# temp-sensor.net
KiCad netlist of a schematic drawn in EAGLE
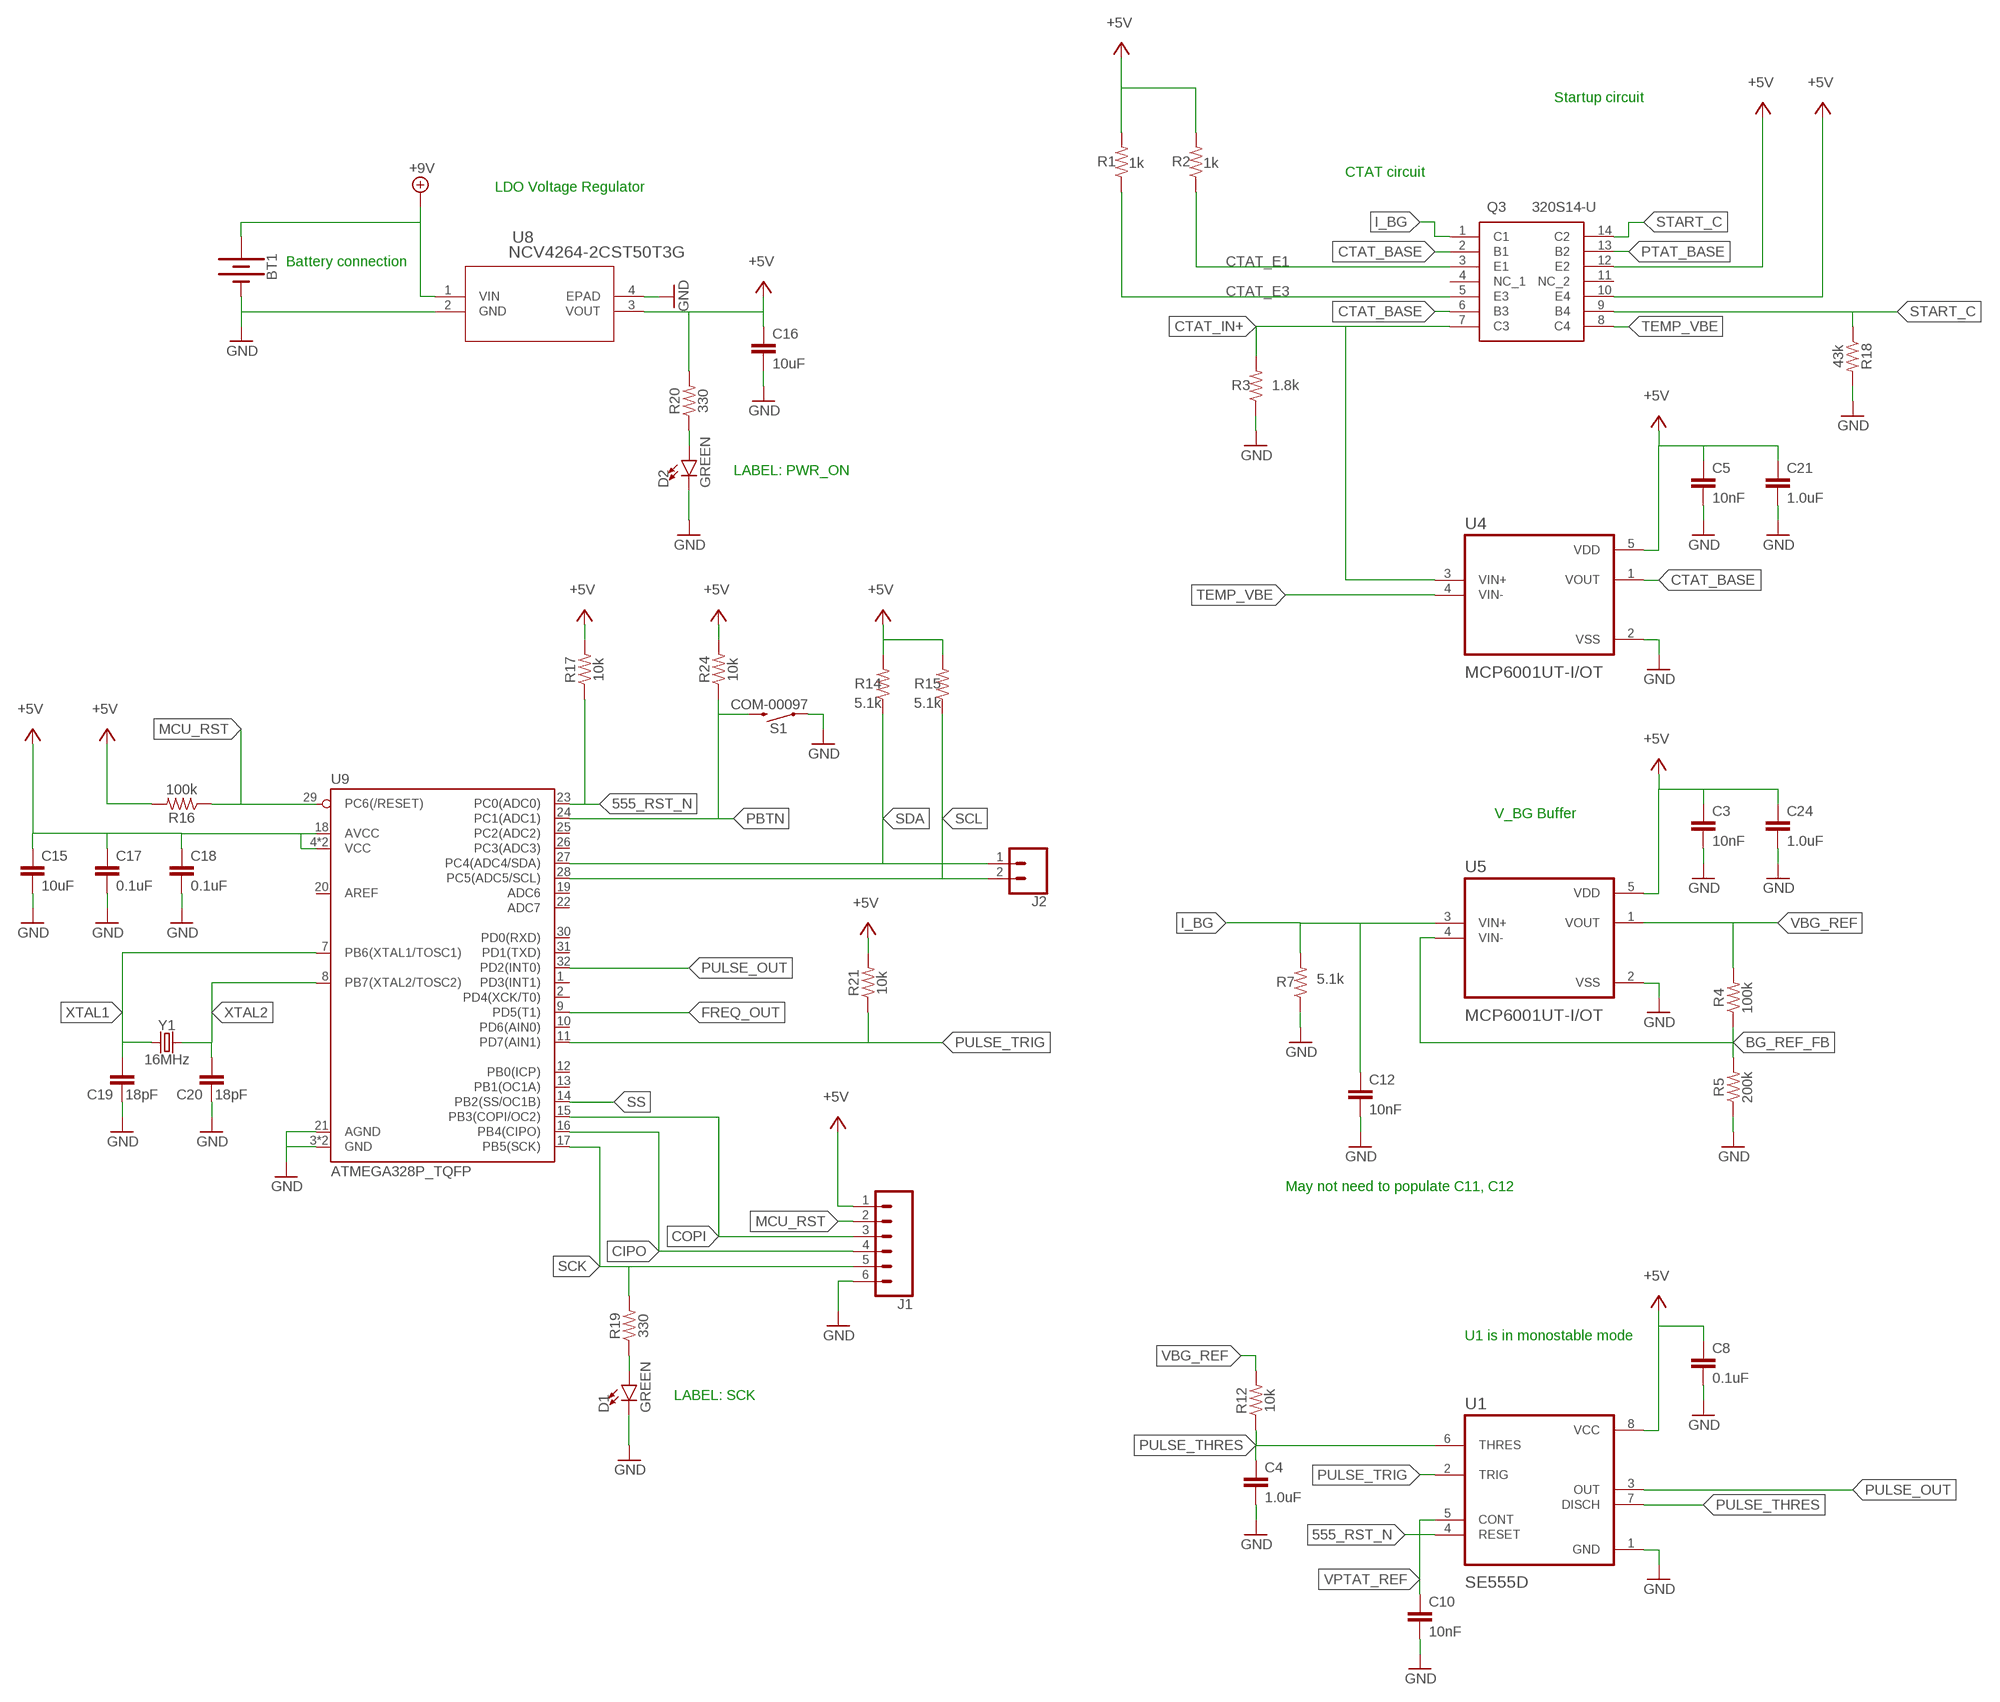
[diagram p0: schematic, sheet 1, part 1 of 2]
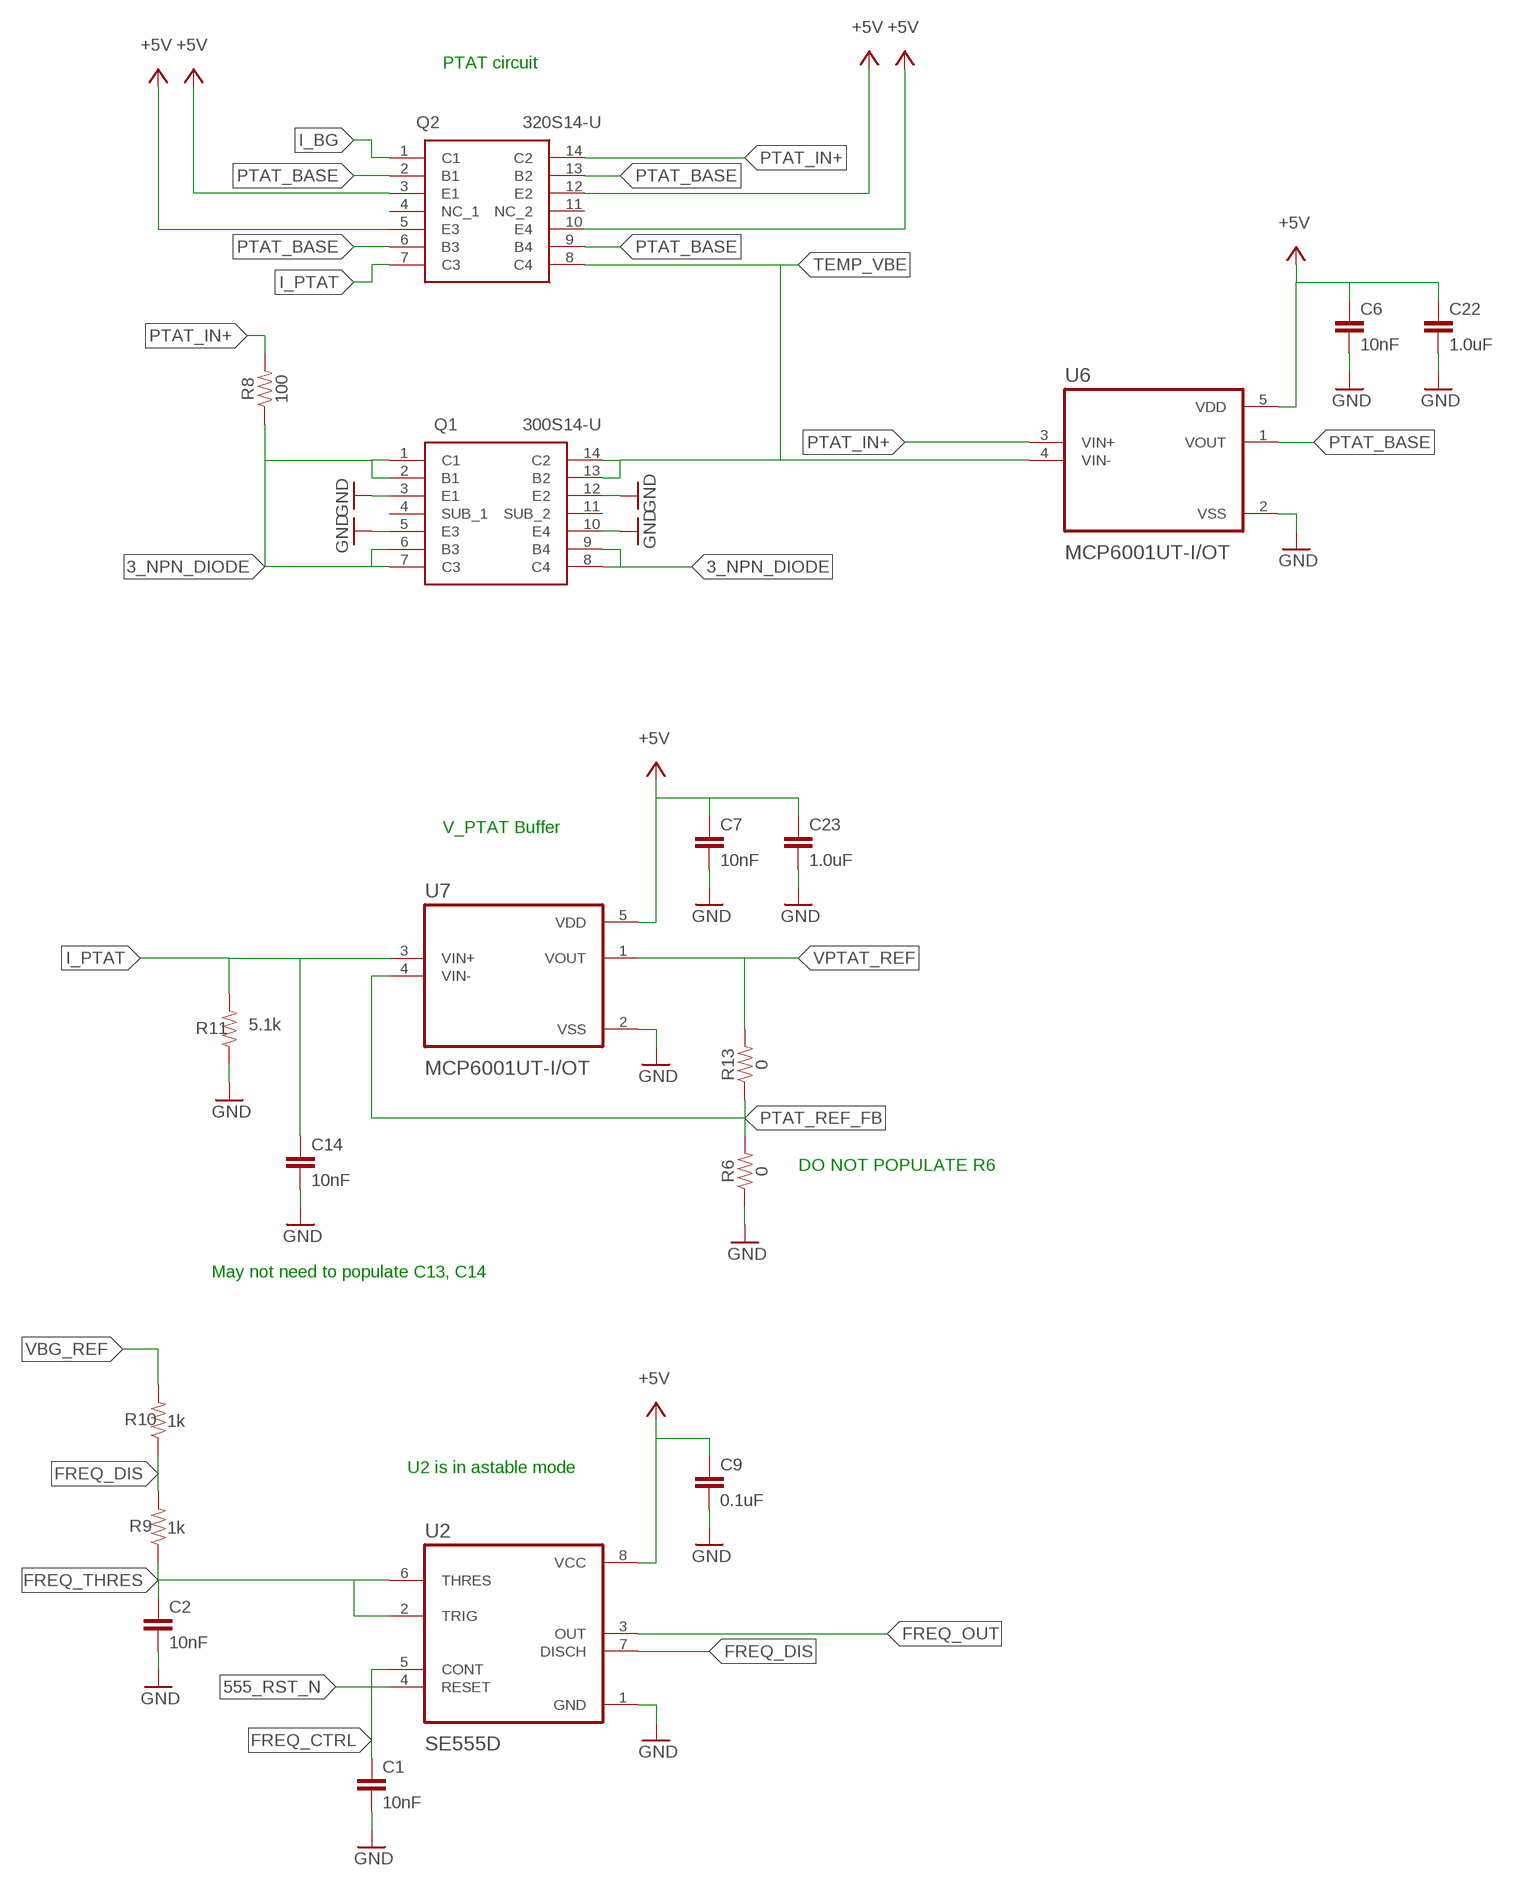
[diagram p1: schematic, sheet 1, part 2 of 2]

(export (version "E")
  (design (tool "Eeschema 10.0.6"))
  (components
    (comp (ref "BT1")
      (value "BATTERY-9V")
      (footprint "eagle-import:BATTCON_9V")
      (libsource (lib "eagle-import") (part "BATTERY-9V"))
    )
    (comp (ref "C1")
      (value "10nF")
      (footprint "eagle-import:0603")
      (libsource (lib "eagle-import") (part "10NF-0603-50V-10%"))
    )
    (comp (ref "C2")
      (value "10nF")
      (footprint "eagle-import:0603")
      (libsource (lib "eagle-import") (part "10NF-0603-50V-10%"))
    )
    (comp (ref "C3")
      (value "10nF")
      (footprint "eagle-import:0603")
      (libsource (lib "eagle-import") (part "10NF-0603-50V-10%"))
    )
    (comp (ref "C4")
      (value "1.0uF")
      (footprint "eagle-import:0603")
      (libsource (lib "eagle-import") (part "1.0UF-0603-16V-10%-X7R"))
    )
    (comp (ref "C5")
      (value "10nF")
      (footprint "eagle-import:0603")
      (libsource (lib "eagle-import") (part "10NF-0603-50V-10%"))
    )
    (comp (ref "C6")
      (value "10nF")
      (footprint "eagle-import:0603")
      (libsource (lib "eagle-import") (part "10NF-0603-50V-10%"))
    )
    (comp (ref "C7")
      (value "10nF")
      (footprint "eagle-import:0603")
      (libsource (lib "eagle-import") (part "10NF-0603-50V-10%"))
    )
    (comp (ref "C8")
      (value "0.1uF")
      (footprint "eagle-import:0603")
      (libsource (lib "eagle-import") (part "0.1UF-0603-25V-10%-X7R-WE"))
    )
    (comp (ref "C9")
      (value "0.1uF")
      (footprint "eagle-import:0603")
      (libsource (lib "eagle-import") (part "0.1UF-0603-25V-10%-X7R-WE"))
    )
    (comp (ref "C10")
      (value "10nF")
      (footprint "eagle-import:0603")
      (libsource (lib "eagle-import") (part "10NF-0603-50V-10%"))
    )
    (comp (ref "C12")
      (value "10nF")
      (footprint "eagle-import:0603")
      (libsource (lib "eagle-import") (part "10NF-0603-50V-10%"))
    )
    (comp (ref "C14")
      (value "10nF")
      (footprint "eagle-import:0603")
      (libsource (lib "eagle-import") (part "10NF-0603-50V-10%"))
    )
    (comp (ref "C15")
      (value "10uF")
      (footprint "eagle-import:0805")
      (libsource (lib "eagle-import") (part "10UF-0805-25V-10%"))
    )
    (comp (ref "C16")
      (value "10uF")
      (footprint "eagle-import:0805")
      (libsource (lib "eagle-import") (part "10UF-0805-25V-10%"))
    )
    (comp (ref "C17")
      (value "0.1uF")
      (footprint "eagle-import:0603")
      (libsource (lib "eagle-import") (part "0.1UF-0603-25V-10%-X7R-WE"))
    )
    (comp (ref "C18")
      (value "0.1uF")
      (footprint "eagle-import:0603")
      (libsource (lib "eagle-import") (part "0.1UF-0603-25V-10%-X7R-WE"))
    )
    (comp (ref "C19")
      (value "18pF")
      (footprint "eagle-import:0603")
      (libsource (lib "eagle-import") (part "18PF-0603-50V-5%"))
    )
    (comp (ref "C20")
      (value "18pF")
      (footprint "eagle-import:0603")
      (libsource (lib "eagle-import") (part "18PF-0603-50V-5%"))
    )
    (comp (ref "C21")
      (value "1.0uF")
      (footprint "eagle-import:0603")
      (libsource (lib "eagle-import") (part "1.0UF-0603-16V-10%-X7R"))
    )
    (comp (ref "C22")
      (value "1.0uF")
      (footprint "eagle-import:0603")
      (libsource (lib "eagle-import") (part "1.0UF-0603-16V-10%-X7R"))
    )
    (comp (ref "C23")
      (value "1.0uF")
      (footprint "eagle-import:0603")
      (libsource (lib "eagle-import") (part "1.0UF-0603-16V-10%-X7R"))
    )
    (comp (ref "C24")
      (value "1.0uF")
      (footprint "eagle-import:0603")
      (libsource (lib "eagle-import") (part "1.0UF-0603-16V-10%-X7R"))
    )
    (comp (ref "D1")
      (value "GREEN")
      (footprint "eagle-import:LED-1206")
      (libsource (lib "eagle-import") (part "LED-GREEN1206"))
    )
    (comp (ref "D2")
      (value "GREEN")
      (footprint "eagle-import:LED-1206")
      (libsource (lib "eagle-import") (part "LED-GREEN1206"))
    )
    (comp (ref "J1")
      (value "CONN_06SILK_FEMALE_PTH")
      (footprint "eagle-import:1X06")
      (libsource (lib "eagle-import") (part "CONN_06SILK_FEMALE_PTH"))
    )
    (comp (ref "J2")
      (value "CONN_02")
      (footprint "eagle-import:1X02")
      (libsource (lib "eagle-import") (part "CONN_02"))
    )
    (comp (ref "Q1")
      (value "300S14-U")
      (footprint "eagle-import:SOIC127P602X175-14N")
      (fields (field (name "MOUSER_PART_NUMBER") "887-300S14-U"))
      (libsource (lib "eagle-import") (part "300S14-U"))
    )
    (comp (ref "Q2")
      (value "320S14-U")
      (footprint "eagle-import:SOIC127P602X175-14N")
      (fields (field (name "MOUSER_PART_NUMBER") "887-320S14-U"))
      (libsource (lib "eagle-import") (part "320S14-U"))
    )
    (comp (ref "Q3")
      (value "320S14-U")
      (footprint "eagle-import:SOIC127P602X175-14N")
      (fields (field (name "MOUSER_PART_NUMBER") "887-320S14-U"))
      (libsource (lib "eagle-import") (part "320S14-U"))
    )
    (comp (ref "R1")
      (value "1k")
      (footprint "eagle-import:0603")
      (libsource (lib "eagle-import") (part "1KOHM-0603-1/10W-1%"))
    )
    (comp (ref "R2")
      (value "1k")
      (footprint "eagle-import:0603")
      (libsource (lib "eagle-import") (part "1KOHM-0603-1/10W-1%"))
    )
    (comp (ref "R3")
      (value "1.8k")
      (footprint "eagle-import:0603")
      (libsource (lib "eagle-import") (part "1.8KOHM-0603-1/10W-1%"))
    )
    (comp (ref "R4")
      (value "100k")
      (footprint "eagle-import:0603")
      (libsource (lib "eagle-import") (part "100KOHM-0603-1/10W-1%"))
    )
    (comp (ref "R5")
      (value "200k")
      (footprint "eagle-import:0603")
      (libsource (lib "eagle-import") (part "200KOHM-0603-1/10W-1%"))
    )
    (comp (ref "R6")
      (value "0")
      (footprint "eagle-import:0603")
      (libsource (lib "eagle-import") (part "0OHM-0603-1/10W"))
    )
    (comp (ref "R7")
      (value "5.1k")
      (footprint "eagle-import:0603")
      (libsource (lib "eagle-import") (part "5.1KOHM5.1KOHM-0603-1/10W-1%"))
    )
    (comp (ref "R8")
      (value "100")
      (footprint "eagle-import:0603")
      (libsource (lib "eagle-import") (part "100OHM-0603-1/10W-1%"))
    )
    (comp (ref "R9")
      (value "1k")
      (footprint "eagle-import:0603")
      (libsource (lib "eagle-import") (part "1KOHM-0603-1/10W-1%"))
    )
    (comp (ref "R10")
      (value "1k")
      (footprint "eagle-import:0603")
      (libsource (lib "eagle-import") (part "1KOHM-0603-1/10W-1%"))
    )
    (comp (ref "R11")
      (value "5.1k")
      (footprint "eagle-import:0603")
      (libsource (lib "eagle-import") (part "5.1KOHM5.1KOHM-0603-1/10W-1%"))
    )
    (comp (ref "R12")
      (value "10k")
      (footprint "eagle-import:0603")
      (libsource (lib "eagle-import") (part "10KOHM-0603-1/10W-1%"))
    )
    (comp (ref "R13")
      (value "0")
      (footprint "eagle-import:0603")
      (libsource (lib "eagle-import") (part "0OHM-0603-1/10W"))
    )
    (comp (ref "R14")
      (value "5.1k")
      (footprint "eagle-import:0603")
      (libsource (lib "eagle-import") (part "5.1KOHM5.1KOHM-0603-1/10W-1%"))
    )
    (comp (ref "R15")
      (value "5.1k")
      (footprint "eagle-import:0603")
      (libsource (lib "eagle-import") (part "5.1KOHM5.1KOHM-0603-1/10W-1%"))
    )
    (comp (ref "R16")
      (value "100k")
      (footprint "eagle-import:0603")
      (libsource (lib "eagle-import") (part "100KOHM-0603-1/10W-1%"))
    )
    (comp (ref "R17")
      (value "10k")
      (footprint "eagle-import:0603")
      (libsource (lib "eagle-import") (part "10KOHM-0603-1/10W-1%"))
    )
    (comp (ref "R18")
      (value "43k")
      (footprint "eagle-import:0603")
      (libsource (lib "eagle-import") (part "43KOHM-0603-1/10W-1%"))
    )
    (comp (ref "R19")
      (value "330")
      (footprint "eagle-import:0603")
      (libsource (lib "eagle-import") (part "330OHM-0603-1/10W-1%"))
    )
    (comp (ref "R20")
      (value "330")
      (footprint "eagle-import:0603")
      (libsource (lib "eagle-import") (part "330OHM-0603-1/10W-1%"))
    )
    (comp (ref "R21")
      (value "10k")
      (footprint "eagle-import:0603")
      (libsource (lib "eagle-import") (part "10KOHM-0603-1/10W-1%"))
    )
    (comp (ref "R24")
      (value "10k")
      (footprint "eagle-import:0603")
      (libsource (lib "eagle-import") (part "10KOHM-0603-1/10W-1%"))
    )
    (comp (ref "S1")
      (value "MOMENTARY-SWITCH-SPST-PTH-6.0MM")
      (footprint "eagle-import:TACTILE_SWITCH_PTH_6.0MM")
      (fields (field (name "SF_SKU") "COM-00097"))
      (libsource (lib "eagle-import") (part "MOMENTARY-SWITCH-SPST-PTH-6.0MM"))
    )
    (comp (ref "U1")
      (value "SE555D")
      (footprint "eagle-import:SOIC127P599X175-8N")
      (fields (field (name "MF") "Texas Instruments"))
      (libsource (lib "eagle-import") (part "SE555D"))
    )
    (comp (ref "U2")
      (value "SE555D")
      (footprint "eagle-import:SOIC127P599X175-8N")
      (fields (field (name "MF") "Texas Instruments"))
      (libsource (lib "eagle-import") (part "SE555D"))
    )
    (comp (ref "U4")
      (value "MCP6001UT-I/OT")
      (footprint "eagle-import:SOT95P270X145-5N")
      (libsource (lib "eagle-import") (part "MCP6001UT-I/OT"))
    )
    (comp (ref "U5")
      (value "MCP6001UT-I/OT")
      (footprint "eagle-import:SOT95P270X145-5N")
      (libsource (lib "eagle-import") (part "MCP6001UT-I/OT"))
    )
    (comp (ref "U6")
      (value "MCP6001UT-I/OT")
      (footprint "eagle-import:SOT95P270X145-5N")
      (libsource (lib "eagle-import") (part "MCP6001UT-I/OT"))
    )
    (comp (ref "U7")
      (value "MCP6001UT-I/OT")
      (footprint "eagle-import:SOT95P270X145-5N")
      (libsource (lib "eagle-import") (part "MCP6001UT-I/OT"))
    )
    (comp (ref "U8")
      (value "NCV4264-2CST50T3G")
      (footprint "eagle-import:SOT-223_ONS")
      (fields (field (name "COPYRIGHT") "Copyright (C) 2024 Ultra Librarian. All rights reserved."))
      (libsource (lib "eagle-import") (part "NCV4264-2CST50T3G"))
    )
    (comp (ref "U9")
      (value "ATMEGA328P_TQFP")
      (footprint "eagle-import:TQFP32-08")
      (libsource (lib "eagle-import") (part "ATMEGA328P_TQFP"))
    )
    (comp (ref "Y1")
      (value "16MHz")
      (footprint "eagle-import:CRYSTAL-SMD-5X3.2-4PAD")
      (libsource (lib "eagle-import") (part "CRYSTAL-16MHZSMD-5X3.2"))
    )
  )
  (nets
    (net (code "1") (name "+5V") (class "Default")
      (node (ref "C15") (pin "1") (pinfunction "1_1") (pintype "passive"))
      (node (ref "C16") (pin "1") (pinfunction "1_1") (pintype "passive"))
      (node (ref "C18") (pin "1") (pinfunction "1_1") (pintype "passive"))
      (node (ref "C21") (pin "1") (pinfunction "1_1") (pintype "passive"))
      (node (ref "C22") (pin "1") (pinfunction "1_1") (pintype "passive"))
      (node (ref "C23") (pin "1") (pinfunction "1_1") (pintype "passive"))
      (node (ref "C24") (pin "1") (pinfunction "1_1") (pintype "passive"))
      (node (ref "C3") (pin "1") (pinfunction "1_1") (pintype "passive"))
      (node (ref "C5") (pin "1") (pinfunction "1_1") (pintype "passive"))
      (node (ref "C6") (pin "1") (pinfunction "1_1") (pintype "passive"))
      (node (ref "C7") (pin "1") (pinfunction "1_1") (pintype "passive"))
      (node (ref "C8") (pin "1") (pinfunction "1_1") (pintype "passive"))
      (node (ref "C9") (pin "1") (pinfunction "1_1") (pintype "passive"))
      (node (ref "J1") (pin "1") (pinfunction "1_1") (pintype "passive"))
      (node (ref "Q2") (pin "10") (pinfunction "E4_10") (pintype "bidirectional"))
      (node (ref "Q2") (pin "12") (pinfunction "E2_12") (pintype "bidirectional"))
      (node (ref "Q2") (pin "3") (pinfunction "E1_3") (pintype "bidirectional"))
      (node (ref "Q2") (pin "5") (pinfunction "E3_5") (pintype "bidirectional"))
      (node (ref "Q3") (pin "10") (pinfunction "E4_10") (pintype "bidirectional"))
      (node (ref "Q3") (pin "12") (pinfunction "E2_12") (pintype "bidirectional"))
      (node (ref "R1") (pin "2") (pinfunction "2_2") (pintype "passive"))
      (node (ref "R14") (pin "2") (pinfunction "2_2") (pintype "passive"))
      (node (ref "R15") (pin "2") (pinfunction "2_2") (pintype "passive"))
      (node (ref "R16") (pin "2") (pinfunction "2_2") (pintype "passive"))
      (node (ref "R17") (pin "2") (pinfunction "2_2") (pintype "passive"))
      (node (ref "R2") (pin "2") (pinfunction "2_2") (pintype "passive"))
      (node (ref "R20") (pin "2") (pinfunction "2_2") (pintype "passive"))
      (node (ref "R21") (pin "2") (pinfunction "2_2") (pintype "passive"))
      (node (ref "R24") (pin "2") (pinfunction "2_2") (pintype "passive"))
      (node (ref "U1") (pin "8") (pinfunction "VCC_8") (pintype "power_in"))
      (node (ref "U2") (pin "8") (pinfunction "VCC_8") (pintype "power_in"))
      (node (ref "U4") (pin "5") (pinfunction "VDD_5") (pintype "power_in"))
      (node (ref "U5") (pin "5") (pinfunction "VDD_5") (pintype "power_in"))
      (node (ref "U6") (pin "5") (pinfunction "VDD_5") (pintype "power_in"))
      (node (ref "U7") (pin "5") (pinfunction "VDD_5") (pintype "power_in"))
      (node (ref "U8") (pin "3") (pinfunction "VOUT_3") (pintype "output"))
      (node (ref "U9") (pin "18") (pinfunction "AVCC_18") (pintype "bidirectional"))
      (node (ref "U9") (pin "4") (pinfunction "VCC_4") (pintype "bidirectional"))
      (node (ref "U9") (pin "6") (pinfunction "VCC_6") (pintype "bidirectional"))
    )
    (net (code "2") (name "+9V") (class "Default")
      (node (ref "BT1") (pin "+") (pinfunction "+_+") (pintype "power_in"))
      (node (ref "U8") (pin "1") (pinfunction "VIN_1") (pintype "passive"))
    )
    (net (code "3") (name "/CTAT_E1") (class "Default")
      (node (ref "Q3") (pin "3") (pinfunction "E1_3") (pintype "bidirectional"))
      (node (ref "R2") (pin "1") (pinfunction "1_1") (pintype "passive"))
    )
    (net (code "4") (name "/CTAT_E3") (class "Default")
      (node (ref "Q3") (pin "5") (pinfunction "E3_5") (pintype "bidirectional"))
      (node (ref "R1") (pin "1") (pinfunction "1_1") (pintype "passive"))
    )
    (net (code "5") (name "3_NPN_DIODE") (class "Default")
      (node (ref "Q1") (pin "1") (pinfunction "C1_1") (pintype "bidirectional"))
      (node (ref "Q1") (pin "2") (pinfunction "B1_2") (pintype "bidirectional"))
      (node (ref "Q1") (pin "6") (pinfunction "B3_6") (pintype "bidirectional"))
      (node (ref "Q1") (pin "7") (pinfunction "C3_7") (pintype "bidirectional"))
      (node (ref "Q1") (pin "8") (pinfunction "C4_8") (pintype "bidirectional"))
      (node (ref "Q1") (pin "9") (pinfunction "B4_9") (pintype "bidirectional"))
      (node (ref "R8") (pin "1") (pinfunction "1_1") (pintype "passive"))
    )
    (net (code "6") (name "555_RST_N") (class "Default")
      (node (ref "R17") (pin "1") (pinfunction "1_1") (pintype "passive"))
      (node (ref "U1") (pin "4") (pinfunction "RESET_4") (pintype "input"))
      (node (ref "U2") (pin "4") (pinfunction "RESET_4") (pintype "input"))
      (node (ref "U9") (pin "23") (pinfunction "PC0(ADC0)_23") (pintype "bidirectional"))
    )
    (net (code "7") (name "BG_REF_FB") (class "Default")
      (node (ref "R4") (pin "1") (pinfunction "1_1") (pintype "passive"))
      (node (ref "R5") (pin "2") (pinfunction "2_2") (pintype "passive"))
      (node (ref "U5") (pin "4") (pinfunction "VIN-_4") (pintype "input"))
    )
    (net (code "8") (name "CIPO") (class "Default")
      (node (ref "J1") (pin "4") (pinfunction "4_4") (pintype "passive"))
      (node (ref "U9") (pin "16") (pinfunction "PB4(CIPO)_16") (pintype "bidirectional"))
    )
    (net (code "9") (name "COPI") (class "Default")
      (node (ref "J1") (pin "3") (pinfunction "3_3") (pintype "passive"))
      (node (ref "U9") (pin "15") (pinfunction "PB3(COPI/OC2)_15") (pintype "bidirectional"))
    )
    (net (code "10") (name "CTAT_BASE") (class "Default")
      (node (ref "Q3") (pin "2") (pinfunction "B1_2") (pintype "bidirectional"))
      (node (ref "Q3") (pin "6") (pinfunction "B3_6") (pintype "bidirectional"))
      (node (ref "U4") (pin "1") (pinfunction "VOUT_1") (pintype "output"))
    )
    (net (code "11") (name "CTAT_IN+") (class "Default")
      (node (ref "Q3") (pin "7") (pinfunction "C3_7") (pintype "bidirectional"))
      (node (ref "R3") (pin "2") (pinfunction "2_2") (pintype "passive"))
      (node (ref "U4") (pin "3") (pinfunction "VIN+_3") (pintype "input"))
    )
    (net (code "12") (name "FREQ_CTRL") (class "Default")
      (node (ref "C1") (pin "1") (pinfunction "1_1") (pintype "passive"))
      (node (ref "U2") (pin "5") (pinfunction "CONT_5") (pintype "bidirectional"))
    )
    (net (code "13") (name "FREQ_DIS") (class "Default")
      (node (ref "R10") (pin "1") (pinfunction "1_1") (pintype "passive"))
      (node (ref "R9") (pin "2") (pinfunction "2_2") (pintype "passive"))
      (node (ref "U2") (pin "7") (pinfunction "DISCH_7") (pintype "output"))
    )
    (net (code "14") (name "FREQ_OUT") (class "Default")
      (node (ref "U2") (pin "3") (pinfunction "OUT_3") (pintype "output"))
      (node (ref "U9") (pin "9") (pinfunction "PD5(T1)_9") (pintype "bidirectional"))
    )
    (net (code "15") (name "FREQ_THRES") (class "Default")
      (node (ref "C2") (pin "1") (pinfunction "1_1") (pintype "passive"))
      (node (ref "R9") (pin "1") (pinfunction "1_1") (pintype "passive"))
      (node (ref "U2") (pin "2") (pinfunction "TRIG_2") (pintype "input"))
      (node (ref "U2") (pin "6") (pinfunction "THRES_6") (pintype "input"))
    )
    (net (code "16") (name "GND") (class "Default")
      (node (ref "BT1") (pin "-") (pinfunction "-_-") (pintype "power_in"))
      (node (ref "C1") (pin "2") (pinfunction "2_2") (pintype "passive"))
      (node (ref "C10") (pin "2") (pinfunction "2_2") (pintype "passive"))
      (node (ref "C12") (pin "2") (pinfunction "2_2") (pintype "passive"))
      (node (ref "C14") (pin "2") (pinfunction "2_2") (pintype "passive"))
      (node (ref "C15") (pin "2") (pinfunction "2_2") (pintype "passive"))
      (node (ref "C16") (pin "2") (pinfunction "2_2") (pintype "passive"))
      (node (ref "C17") (pin "2") (pinfunction "2_2") (pintype "passive"))
      (node (ref "C18") (pin "2") (pinfunction "2_2") (pintype "passive"))
      (node (ref "C19") (pin "1") (pinfunction "1_1") (pintype "passive"))
      (node (ref "C2") (pin "2") (pinfunction "2_2") (pintype "passive"))
      (node (ref "C20") (pin "1") (pinfunction "1_1") (pintype "passive"))
      (node (ref "C21") (pin "2") (pinfunction "2_2") (pintype "passive"))
      (node (ref "C22") (pin "2") (pinfunction "2_2") (pintype "passive"))
      (node (ref "C23") (pin "2") (pinfunction "2_2") (pintype "passive"))
      (node (ref "C24") (pin "2") (pinfunction "2_2") (pintype "passive"))
      (node (ref "C3") (pin "2") (pinfunction "2_2") (pintype "passive"))
      (node (ref "C4") (pin "2") (pinfunction "2_2") (pintype "passive"))
      (node (ref "C5") (pin "2") (pinfunction "2_2") (pintype "passive"))
      (node (ref "C6") (pin "2") (pinfunction "2_2") (pintype "passive"))
      (node (ref "C7") (pin "2") (pinfunction "2_2") (pintype "passive"))
      (node (ref "C8") (pin "2") (pinfunction "2_2") (pintype "passive"))
      (node (ref "C9") (pin "2") (pinfunction "2_2") (pintype "passive"))
      (node (ref "D1") (pin "C") (pinfunction "C_C") (pintype "passive"))
      (node (ref "D2") (pin "C") (pinfunction "C_C") (pintype "passive"))
      (node (ref "J1") (pin "6") (pinfunction "6_6") (pintype "passive"))
      (node (ref "Q1") (pin "10") (pinfunction "E4_10") (pintype "bidirectional"))
      (node (ref "Q1") (pin "12") (pinfunction "E2_12") (pintype "bidirectional"))
      (node (ref "Q1") (pin "3") (pinfunction "E1_3") (pintype "bidirectional"))
      (node (ref "Q1") (pin "5") (pinfunction "E3_5") (pintype "bidirectional"))
      (node (ref "R11") (pin "1") (pinfunction "1_1") (pintype "passive"))
      (node (ref "R18") (pin "2") (pinfunction "2_2") (pintype "passive"))
      (node (ref "R3") (pin "1") (pinfunction "1_1") (pintype "passive"))
      (node (ref "R5") (pin "1") (pinfunction "1_1") (pintype "passive"))
      (node (ref "R6") (pin "1") (pinfunction "1_1") (pintype "passive"))
      (node (ref "R7") (pin "1") (pinfunction "1_1") (pintype "passive"))
      (node (ref "S1") (pin "1") (pinfunction "1_1") (pintype "passive"))
      (node (ref "U1") (pin "1") (pinfunction "GND_1") (pintype "power_in"))
      (node (ref "U2") (pin "1") (pinfunction "GND_1") (pintype "power_in"))
      (node (ref "U4") (pin "2") (pinfunction "VSS_2") (pintype "power_in"))
      (node (ref "U5") (pin "2") (pinfunction "VSS_2") (pintype "power_in"))
      (node (ref "U6") (pin "2") (pinfunction "VSS_2") (pintype "power_in"))
      (node (ref "U7") (pin "2") (pinfunction "VSS_2") (pintype "power_in"))
      (node (ref "U8") (pin "2") (pinfunction "GND_2") (pintype "passive"))
      (node (ref "U8") (pin "4") (pinfunction "EPAD_4") (pintype "passive"))
      (node (ref "U9") (pin "21") (pinfunction "AGND_21") (pintype "bidirectional"))
      (node (ref "U9") (pin "3") (pinfunction "GND_3") (pintype "bidirectional"))
      (node (ref "U9") (pin "5") (pinfunction "GND_5") (pintype "bidirectional"))
    )
    (net (code "17") (name "I_BG") (class "Default")
      (node (ref "C12") (pin "1") (pinfunction "1_1") (pintype "passive"))
      (node (ref "Q2") (pin "1") (pinfunction "C1_1") (pintype "bidirectional"))
      (node (ref "Q3") (pin "1") (pinfunction "C1_1") (pintype "bidirectional"))
      (node (ref "R7") (pin "2") (pinfunction "2_2") (pintype "passive"))
      (node (ref "U5") (pin "3") (pinfunction "VIN+_3") (pintype "input"))
    )
    (net (code "18") (name "I_PTAT") (class "Default")
      (node (ref "C14") (pin "1") (pinfunction "1_1") (pintype "passive"))
      (node (ref "Q2") (pin "7") (pinfunction "C3_7") (pintype "bidirectional"))
      (node (ref "R11") (pin "2") (pinfunction "2_2") (pintype "passive"))
      (node (ref "U7") (pin "3") (pinfunction "VIN+_3") (pintype "input"))
    )
    (net (code "19") (name "MCU_RST") (class "Default")
      (node (ref "J1") (pin "2") (pinfunction "2_2") (pintype "passive"))
      (node (ref "R16") (pin "1") (pinfunction "1_1") (pintype "passive"))
      (node (ref "U9") (pin "29") (pinfunction "PC6(/RESET)_29") (pintype "bidirectional"))
    )
    (net (code "20") (name "Net-(D1-PadA)") (class "Default")
      (node (ref "D1") (pin "A") (pinfunction "A_A") (pintype "passive"))
      (node (ref "R19") (pin "1") (pinfunction "1_1") (pintype "passive"))
    )
    (net (code "21") (name "Net-(D2-PadA)") (class "Default")
      (node (ref "D2") (pin "A") (pinfunction "A_A") (pintype "passive"))
      (node (ref "R20") (pin "1") (pinfunction "1_1") (pintype "passive"))
    )
    (net (code "22") (name "PBTN") (class "Default")
      (node (ref "R24") (pin "1") (pinfunction "1_1") (pintype "passive"))
      (node (ref "S1") (pin "3") (pinfunction "2_3") (pintype "passive"))
      (node (ref "U9") (pin "24") (pinfunction "PC1(ADC1)_24") (pintype "bidirectional"))
    )
    (net (code "23") (name "PTAT_BASE") (class "Default")
      (node (ref "Q2") (pin "13") (pinfunction "B2_13") (pintype "bidirectional"))
      (node (ref "Q2") (pin "2") (pinfunction "B1_2") (pintype "bidirectional"))
      (node (ref "Q2") (pin "6") (pinfunction "B3_6") (pintype "bidirectional"))
      (node (ref "Q2") (pin "9") (pinfunction "B4_9") (pintype "bidirectional"))
      (node (ref "Q3") (pin "13") (pinfunction "B2_13") (pintype "bidirectional"))
      (node (ref "U6") (pin "1") (pinfunction "VOUT_1") (pintype "output"))
    )
    (net (code "24") (name "PTAT_IN+") (class "Default")
      (node (ref "Q2") (pin "14") (pinfunction "C2_14") (pintype "bidirectional"))
      (node (ref "R8") (pin "2") (pinfunction "2_2") (pintype "passive"))
      (node (ref "U6") (pin "3") (pinfunction "VIN+_3") (pintype "input"))
    )
    (net (code "25") (name "PTAT_REF_FB") (class "Default")
      (node (ref "R13") (pin "1") (pinfunction "1_1") (pintype "passive"))
      (node (ref "R6") (pin "2") (pinfunction "2_2") (pintype "passive"))
      (node (ref "U7") (pin "4") (pinfunction "VIN-_4") (pintype "input"))
    )
    (net (code "26") (name "PULSE_OUT") (class "Default")
      (node (ref "U1") (pin "3") (pinfunction "OUT_3") (pintype "output"))
      (node (ref "U9") (pin "32") (pinfunction "PD2(INT0)_32") (pintype "bidirectional"))
    )
    (net (code "27") (name "PULSE_THRES") (class "Default")
      (node (ref "C4") (pin "1") (pinfunction "1_1") (pintype "passive"))
      (node (ref "R12") (pin "1") (pinfunction "1_1") (pintype "passive"))
      (node (ref "U1") (pin "6") (pinfunction "THRES_6") (pintype "input"))
      (node (ref "U1") (pin "7") (pinfunction "DISCH_7") (pintype "output"))
    )
    (net (code "28") (name "PULSE_TRIG") (class "Default")
      (node (ref "R21") (pin "1") (pinfunction "1_1") (pintype "passive"))
      (node (ref "U1") (pin "2") (pinfunction "TRIG_2") (pintype "input"))
      (node (ref "U9") (pin "11") (pinfunction "PD7(AIN1)_11") (pintype "bidirectional"))
    )
    (net (code "29") (name "SCK") (class "Default")
      (node (ref "J1") (pin "5") (pinfunction "5_5") (pintype "passive"))
      (node (ref "R19") (pin "2") (pinfunction "2_2") (pintype "passive"))
      (node (ref "U9") (pin "17") (pinfunction "PB5(SCK)_17") (pintype "bidirectional"))
    )
    (net (code "30") (name "SCL") (class "Default")
      (node (ref "J2") (pin "2") (pinfunction "2_2") (pintype "passive"))
      (node (ref "R15") (pin "1") (pinfunction "1_1") (pintype "passive"))
      (node (ref "U9") (pin "28") (pinfunction "PC5(ADC5/SCL)_28") (pintype "bidirectional"))
    )
    (net (code "31") (name "SDA") (class "Default")
      (node (ref "J2") (pin "1") (pinfunction "1_1") (pintype "passive"))
      (node (ref "R14") (pin "1") (pinfunction "1_1") (pintype "passive"))
      (node (ref "U9") (pin "27") (pinfunction "PC4(ADC4/SDA)_27") (pintype "bidirectional"))
    )
    (net (code "32") (name "SS") (class "Default")
      (node (ref "U9") (pin "14") (pinfunction "PB2(SS/OC1B)_14") (pintype "bidirectional"))
    )
    (net (code "33") (name "START_C") (class "Default")
      (node (ref "Q3") (pin "14") (pinfunction "C2_14") (pintype "bidirectional"))
      (node (ref "Q3") (pin "9") (pinfunction "B4_9") (pintype "bidirectional"))
      (node (ref "R18") (pin "1") (pinfunction "1_1") (pintype "passive"))
    )
    (net (code "34") (name "TEMP_VBE") (class "Default")
      (node (ref "Q1") (pin "13") (pinfunction "B2_13") (pintype "bidirectional"))
      (node (ref "Q1") (pin "14") (pinfunction "C2_14") (pintype "bidirectional"))
      (node (ref "Q2") (pin "8") (pinfunction "C4_8") (pintype "bidirectional"))
      (node (ref "Q3") (pin "8") (pinfunction "C4_8") (pintype "bidirectional"))
      (node (ref "U4") (pin "4") (pinfunction "VIN-_4") (pintype "input"))
      (node (ref "U6") (pin "4") (pinfunction "VIN-_4") (pintype "input"))
    )
    (net (code "35") (name "VBG_REF") (class "Default")
      (node (ref "R10") (pin "2") (pinfunction "2_2") (pintype "passive"))
      (node (ref "R12") (pin "2") (pinfunction "2_2") (pintype "passive"))
      (node (ref "R4") (pin "2") (pinfunction "2_2") (pintype "passive"))
      (node (ref "U5") (pin "1") (pinfunction "VOUT_1") (pintype "output"))
    )
    (net (code "36") (name "VPTAT_REF") (class "Default")
      (node (ref "C10") (pin "1") (pinfunction "1_1") (pintype "passive"))
      (node (ref "R13") (pin "2") (pinfunction "2_2") (pintype "passive"))
      (node (ref "U1") (pin "5") (pinfunction "CONT_5") (pintype "bidirectional"))
      (node (ref "U7") (pin "1") (pinfunction "VOUT_1") (pintype "output"))
    )
    (net (code "37") (name "XTAL1") (class "Default")
      (node (ref "C19") (pin "2") (pinfunction "2_2") (pintype "passive"))
      (node (ref "U9") (pin "7") (pinfunction "PB6(XTAL1/TOSC1)_7") (pintype "bidirectional"))
      (node (ref "Y1") (pin "1") (pinfunction "1_1") (pintype "passive"))
    )
    (net (code "38") (name "XTAL2") (class "Default")
      (node (ref "C20") (pin "2") (pinfunction "2_2") (pintype "passive"))
      (node (ref "U9") (pin "8") (pinfunction "PB7(XTAL2/TOSC2)_8") (pintype "bidirectional"))
      (node (ref "Y1") (pin "3") (pinfunction "2_3") (pintype "passive"))
    )
    (net (code "39") (name "unconnected-(C17-Pad1)") (class "Default")
      (node (ref "C17") (pin "1") (pinfunction "1_1") (pintype "passive"))
    )
    (net (code "40") (name "unconnected-(Q1-SUB_1-Pad4)") (class "Default")
      (node (ref "Q1") (pin "4") (pinfunction "SUB_1_4") (pintype "bidirectional"))
    )
    (net (code "41") (name "unconnected-(Q1-SUB_2-Pad11)") (class "Default")
      (node (ref "Q1") (pin "11") (pinfunction "SUB_2_11") (pintype "bidirectional"))
    )
    (net (code "42") (name "unconnected-(Q2-NC_1-Pad4)") (class "Default")
      (node (ref "Q2") (pin "4") (pinfunction "NC_1_4") (pintype "bidirectional"))
    )
    (net (code "43") (name "unconnected-(Q2-NC_2-Pad11)") (class "Default")
      (node (ref "Q2") (pin "11") (pinfunction "NC_2_11") (pintype "bidirectional"))
    )
    (net (code "44") (name "unconnected-(Q3-NC_1-Pad4)") (class "Default")
      (node (ref "Q3") (pin "4") (pinfunction "NC_1_4") (pintype "bidirectional"))
    )
    (net (code "45") (name "unconnected-(Q3-NC_2-Pad11)") (class "Default")
      (node (ref "Q3") (pin "11") (pinfunction "NC_2_11") (pintype "bidirectional"))
    )
    (net (code "46") (name "unconnected-(U9-ADC6-Pad19)") (class "Default")
      (node (ref "U9") (pin "19") (pinfunction "ADC6_19") (pintype "bidirectional"))
    )
    (net (code "47") (name "unconnected-(U9-ADC7-Pad22)") (class "Default")
      (node (ref "U9") (pin "22") (pinfunction "ADC7_22") (pintype "bidirectional"))
    )
    (net (code "48") (name "unconnected-(U9-AREF-Pad20)") (class "Default")
      (node (ref "U9") (pin "20") (pinfunction "AREF_20") (pintype "bidirectional"))
    )
    (net (code "49") (name "unconnected-(U9-PB0(ICP)-Pad12)") (class "Default")
      (node (ref "U9") (pin "12") (pinfunction "PB0(ICP)_12") (pintype "bidirectional"))
    )
    (net (code "50") (name "unconnected-(U9-PB1(OC1A)-Pad13)") (class "Default")
      (node (ref "U9") (pin "13") (pinfunction "PB1(OC1A)_13") (pintype "bidirectional"))
    )
    (net (code "51") (name "unconnected-(U9-PC2(ADC2)-Pad25)") (class "Default")
      (node (ref "U9") (pin "25") (pinfunction "PC2(ADC2)_25") (pintype "bidirectional"))
    )
    (net (code "52") (name "unconnected-(U9-PC3(ADC3)-Pad26)") (class "Default")
      (node (ref "U9") (pin "26") (pinfunction "PC3(ADC3)_26") (pintype "bidirectional"))
    )
    (net (code "53") (name "unconnected-(U9-PD0(RXD)-Pad30)") (class "Default")
      (node (ref "U9") (pin "30") (pinfunction "PD0(RXD)_30") (pintype "bidirectional"))
    )
    (net (code "54") (name "unconnected-(U9-PD1(TXD)-Pad31)") (class "Default")
      (node (ref "U9") (pin "31") (pinfunction "PD1(TXD)_31") (pintype "bidirectional"))
    )
    (net (code "55") (name "unconnected-(U9-PD3(INT1)-Pad1)") (class "Default")
      (node (ref "U9") (pin "1") (pinfunction "PD3(INT1)_1") (pintype "bidirectional"))
    )
    (net (code "56") (name "unconnected-(U9-PD4(XCK{slash}T0)-Pad2)") (class "Default")
      (node (ref "U9") (pin "2") (pinfunction "PD4(XCK/T0)_2") (pintype "bidirectional"))
    )
    (net (code "57") (name "unconnected-(U9-PD6(AIN0)-Pad10)") (class "Default")
      (node (ref "U9") (pin "10") (pinfunction "PD6(AIN0)_10") (pintype "bidirectional"))
    )
  )
)
